# PMW3360-breakout_01.net
KiCad netlist of a schematic drawn in EAGLE
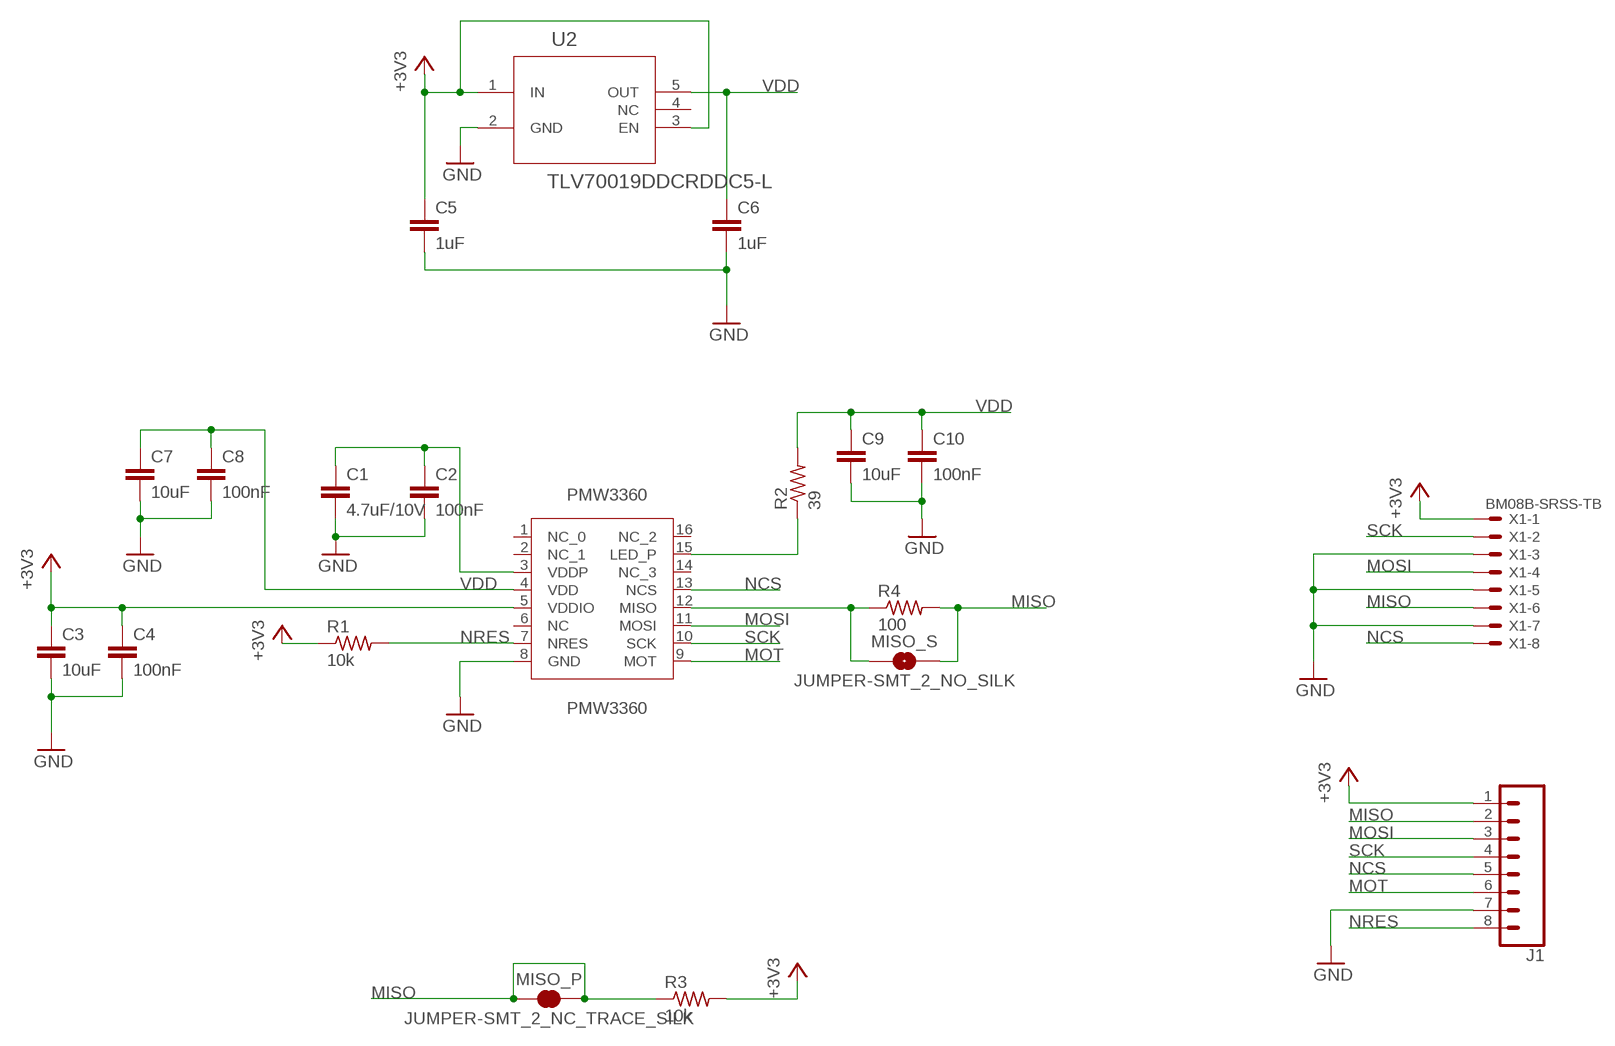
[diagram p0: schematic, sheet 1]

(export (version "E")
  (design (tool "Eeschema 10.0.6"))
  (components
    (comp (ref "C1")
      (value "4.7uF/10V")
      (footprint "eagle-import:C0603")
      (libsource (lib "eagle-import") (part "C-EUC0603"))
    )
    (comp (ref "C2")
      (value "100nF")
      (footprint "eagle-import:C0402")
      (libsource (lib "eagle-import") (part "C-EUC0402"))
    )
    (comp (ref "C3")
      (value "10uF")
      (footprint "eagle-import:C0402")
      (libsource (lib "eagle-import") (part "C-EUC0402"))
    )
    (comp (ref "C4")
      (value "100nF")
      (footprint "eagle-import:C0402")
      (libsource (lib "eagle-import") (part "C-EUC0402"))
    )
    (comp (ref "C5")
      (value "1uF")
      (footprint "eagle-import:C0402")
      (libsource (lib "eagle-import") (part "C-EUC0402"))
    )
    (comp (ref "C6")
      (value "1uF")
      (footprint "eagle-import:C0402")
      (libsource (lib "eagle-import") (part "C-EUC0402"))
    )
    (comp (ref "C7")
      (value "10uF")
      (footprint "eagle-import:C0402")
      (libsource (lib "eagle-import") (part "C-EUC0402"))
    )
    (comp (ref "C8")
      (value "100nF")
      (footprint "eagle-import:C0402")
      (libsource (lib "eagle-import") (part "C-EUC0402"))
    )
    (comp (ref "C9")
      (value "10uF")
      (footprint "eagle-import:C0402")
      (libsource (lib "eagle-import") (part "C-EUC0402"))
    )
    (comp (ref "C10")
      (value "100nF")
      (footprint "eagle-import:C0402")
      (libsource (lib "eagle-import") (part "C-EUC0402"))
    )
    (comp (ref "J1")
      (value "CONN_08\"")
      (footprint "eagle-import:1X08")
      (libsource (lib "eagle-import") (part "CONN_08{dblquote}"))
    )
    (comp (ref "MISO_P")
      (value "JUMPER-SMT_2_NC_TRACE_SILK")
      (footprint "eagle-import:SMT-JUMPER_2_NC_TRACE_SILK")
      (libsource (lib "eagle-import") (part "JUMPER-SMT_2_NC_TRACE_SILK"))
    )
    (comp (ref "MISO_S")
      (value "JUMPER-SMT_2_NO_SILK")
      (footprint "eagle-import:SMT-JUMPER_2_NO_SILK")
      (libsource (lib "eagle-import") (part "JUMPER-SMT_2_NO_SILK"))
    )
    (comp (ref "PMW3360")
      (value "PMW3360")
      (footprint "eagle-import:PMW3360")
      (libsource (lib "eagle-import") (part "PMW3360"))
    )
    (comp (ref "R1")
      (value "10k")
      (footprint "eagle-import:R0402")
      (libsource (lib "eagle-import") (part "R-US_R0402"))
    )
    (comp (ref "R2")
      (value "39")
      (footprint "eagle-import:R0402")
      (libsource (lib "eagle-import") (part "R-US_R0402"))
    )
    (comp (ref "R3")
      (value "10k")
      (footprint "eagle-import:R0402")
      (libsource (lib "eagle-import") (part "R-US_R0402"))
    )
    (comp (ref "R4")
      (value "100")
      (footprint "eagle-import:R0402")
      (libsource (lib "eagle-import") (part "R-US_R0402"))
    )
    (comp (ref "U2")
      (value "TLV70019DDCRDDC5-L")
      (footprint "eagle-import:DDC5-L")
      (fields
        (field (name "MANUFACTURER_PART_NUMBER") "TLV70019DDCR")
        (field (name "COPYRIGHT") "Copyright (C) 2024 Ultra Librarian. All rights reserved.")
      )
      (libsource (lib "eagle-import") (part "TLV70019DDCRDDC5-L"))
    )
    (comp (ref "X1")
      (value "BM08B-SRSS-TB")
      (footprint "eagle-import:BM08B-SRSS-TB")
      (libsource (lib "eagle-import") (part "?M08B-SRSS-TBB"))
    )
  )
  (nets
    (net (code "1") (name "+3V3") (class "Default")
      (node (ref "C3") (pin "1") (pinfunction "1_1") (pintype "passive"))
      (node (ref "C4") (pin "1") (pinfunction "1_1") (pintype "passive"))
      (node (ref "C5") (pin "1") (pinfunction "1_1") (pintype "passive"))
      (node (ref "J1") (pin "1") (pinfunction "1_1") (pintype "passive"))
      (node (ref "PMW3360") (pin "5") (pinfunction "VDDIO_5") (pintype "power_in"))
      (node (ref "R1") (pin "1") (pinfunction "1_1") (pintype "passive"))
      (node (ref "R3") (pin "2") (pinfunction "2_2") (pintype "passive"))
      (node (ref "U2") (pin "1") (pinfunction "IN_1") (pintype "input"))
      (node (ref "U2") (pin "3") (pinfunction "EN_3") (pintype "passive"))
      (node (ref "X1") (pin "1") (pinfunction "S_1") (pintype "passive"))
    )
    (net (code "2") (name "/MISO") (class "Default")
      (node (ref "J1") (pin "2") (pinfunction "2_2") (pintype "passive"))
      (node (ref "MISO_P") (pin "1") (pinfunction "1_1") (pintype "passive"))
      (node (ref "MISO_P") (pin "2") (pinfunction "2_2") (pintype "passive"))
      (node (ref "MISO_S") (pin "2") (pinfunction "2_2") (pintype "passive"))
      (node (ref "R3") (pin "1") (pinfunction "1_1") (pintype "passive"))
      (node (ref "R4") (pin "2") (pinfunction "2_2") (pintype "passive"))
      (node (ref "X1") (pin "6") (pinfunction "S_6") (pintype "passive"))
    )
    (net (code "3") (name "/MOSI") (class "Default")
      (node (ref "J1") (pin "3") (pinfunction "3_3") (pintype "passive"))
      (node (ref "PMW3360") (pin "11") (pinfunction "MOSI_11") (pintype "input"))
      (node (ref "X1") (pin "4") (pinfunction "S_4") (pintype "passive"))
    )
    (net (code "4") (name "/MOT") (class "Default")
      (node (ref "J1") (pin "6") (pinfunction "6_6") (pintype "passive"))
      (node (ref "PMW3360") (pin "9") (pinfunction "MOT_9") (pintype "output"))
    )
    (net (code "5") (name "/NCS") (class "Default")
      (node (ref "J1") (pin "5") (pinfunction "5_5") (pintype "passive"))
      (node (ref "PMW3360") (pin "13") (pinfunction "NCS_13") (pintype "input"))
      (node (ref "X1") (pin "8") (pinfunction "S_8") (pintype "passive"))
    )
    (net (code "6") (name "/NRES") (class "Default")
      (node (ref "J1") (pin "8") (pinfunction "8_8") (pintype "passive"))
      (node (ref "PMW3360") (pin "7") (pinfunction "NRES_7") (pintype "input"))
      (node (ref "R1") (pin "2") (pinfunction "2_2") (pintype "passive"))
    )
    (net (code "7") (name "/SCK") (class "Default")
      (node (ref "J1") (pin "4") (pinfunction "4_4") (pintype "passive"))
      (node (ref "PMW3360") (pin "10") (pinfunction "SCK_10") (pintype "input"))
      (node (ref "X1") (pin "2") (pinfunction "S_2") (pintype "passive"))
    )
    (net (code "8") (name "/VDD") (class "Default")
      (node (ref "C10") (pin "1") (pinfunction "1_1") (pintype "passive"))
      (node (ref "C6") (pin "1") (pinfunction "1_1") (pintype "passive"))
      (node (ref "C7") (pin "1") (pinfunction "1_1") (pintype "passive"))
      (node (ref "C8") (pin "1") (pinfunction "1_1") (pintype "passive"))
      (node (ref "C9") (pin "1") (pinfunction "1_1") (pintype "passive"))
      (node (ref "PMW3360") (pin "4") (pinfunction "VDD_4") (pintype "power_in"))
      (node (ref "R2") (pin "2") (pinfunction "2_2") (pintype "passive"))
      (node (ref "U2") (pin "5") (pinfunction "OUT_5") (pintype "output"))
    )
    (net (code "9") (name "GND") (class "Default")
      (node (ref "C1") (pin "2") (pinfunction "2_2") (pintype "passive"))
      (node (ref "C10") (pin "2") (pinfunction "2_2") (pintype "passive"))
      (node (ref "C2") (pin "2") (pinfunction "2_2") (pintype "passive"))
      (node (ref "C3") (pin "2") (pinfunction "2_2") (pintype "passive"))
      (node (ref "C4") (pin "2") (pinfunction "2_2") (pintype "passive"))
      (node (ref "C5") (pin "2") (pinfunction "2_2") (pintype "passive"))
      (node (ref "C6") (pin "2") (pinfunction "2_2") (pintype "passive"))
      (node (ref "C7") (pin "2") (pinfunction "2_2") (pintype "passive"))
      (node (ref "C8") (pin "2") (pinfunction "2_2") (pintype "passive"))
      (node (ref "C9") (pin "2") (pinfunction "2_2") (pintype "passive"))
      (node (ref "J1") (pin "7") (pinfunction "7_7") (pintype "passive"))
      (node (ref "PMW3360") (pin "8") (pinfunction "GND_8") (pintype "power_in"))
      (node (ref "U2") (pin "2") (pinfunction "GND_2") (pintype "power_in"))
      (node (ref "X1") (pin "3") (pinfunction "S_3") (pintype "passive"))
      (node (ref "X1") (pin "5") (pinfunction "S_5") (pintype "passive"))
      (node (ref "X1") (pin "7") (pinfunction "S_7") (pintype "passive"))
    )
    (net (code "10") (name "Net-(PMW3360-LED_P)") (class "Default")
      (node (ref "PMW3360") (pin "15") (pinfunction "LED_P_15") (pintype "input"))
      (node (ref "R2") (pin "1") (pinfunction "1_1") (pintype "passive"))
    )
    (net (code "11") (name "Net-(PMW3360-MISO)") (class "Default")
      (node (ref "MISO_S") (pin "1") (pinfunction "1_1") (pintype "passive"))
      (node (ref "PMW3360") (pin "12") (pinfunction "MISO_12") (pintype "output"))
      (node (ref "R4") (pin "1") (pinfunction "1_1") (pintype "passive"))
    )
    (net (code "12") (name "Net-(PMW3360-VDDP)") (class "Default")
      (node (ref "C1") (pin "1") (pinfunction "1_1") (pintype "passive"))
      (node (ref "C2") (pin "1") (pinfunction "1_1") (pintype "passive"))
      (node (ref "PMW3360") (pin "3") (pinfunction "VDDP_3") (pintype "power_in"))
    )
    (net (code "13") (name "unconnected-(PMW3360-NC-Pad6)") (class "Default")
      (node (ref "PMW3360") (pin "6") (pinfunction "NC_6") (pintype "no_connect"))
    )
    (net (code "14") (name "unconnected-(PMW3360-NC_0-Pad1)") (class "Default")
      (node (ref "PMW3360") (pin "1") (pinfunction "NC_0_1") (pintype "no_connect"))
    )
    (net (code "15") (name "unconnected-(PMW3360-NC_1-Pad2)") (class "Default")
      (node (ref "PMW3360") (pin "2") (pinfunction "NC_1_2") (pintype "no_connect"))
    )
    (net (code "16") (name "unconnected-(PMW3360-NC_2-Pad16)") (class "Default")
      (node (ref "PMW3360") (pin "16") (pinfunction "NC_2_16") (pintype "no_connect"))
    )
    (net (code "17") (name "unconnected-(PMW3360-NC_3-Pad14)") (class "Default")
      (node (ref "PMW3360") (pin "14") (pinfunction "NC_3_14") (pintype "no_connect"))
    )
    (net (code "18") (name "unconnected-(U2-NC-Pad4)") (class "Default")
      (node (ref "U2") (pin "4") (pinfunction "NC_4") (pintype "passive"))
    )
  )
)
